# Mirley_USB-UART.net
KiCad netlist of a schematic drawn in EAGLE
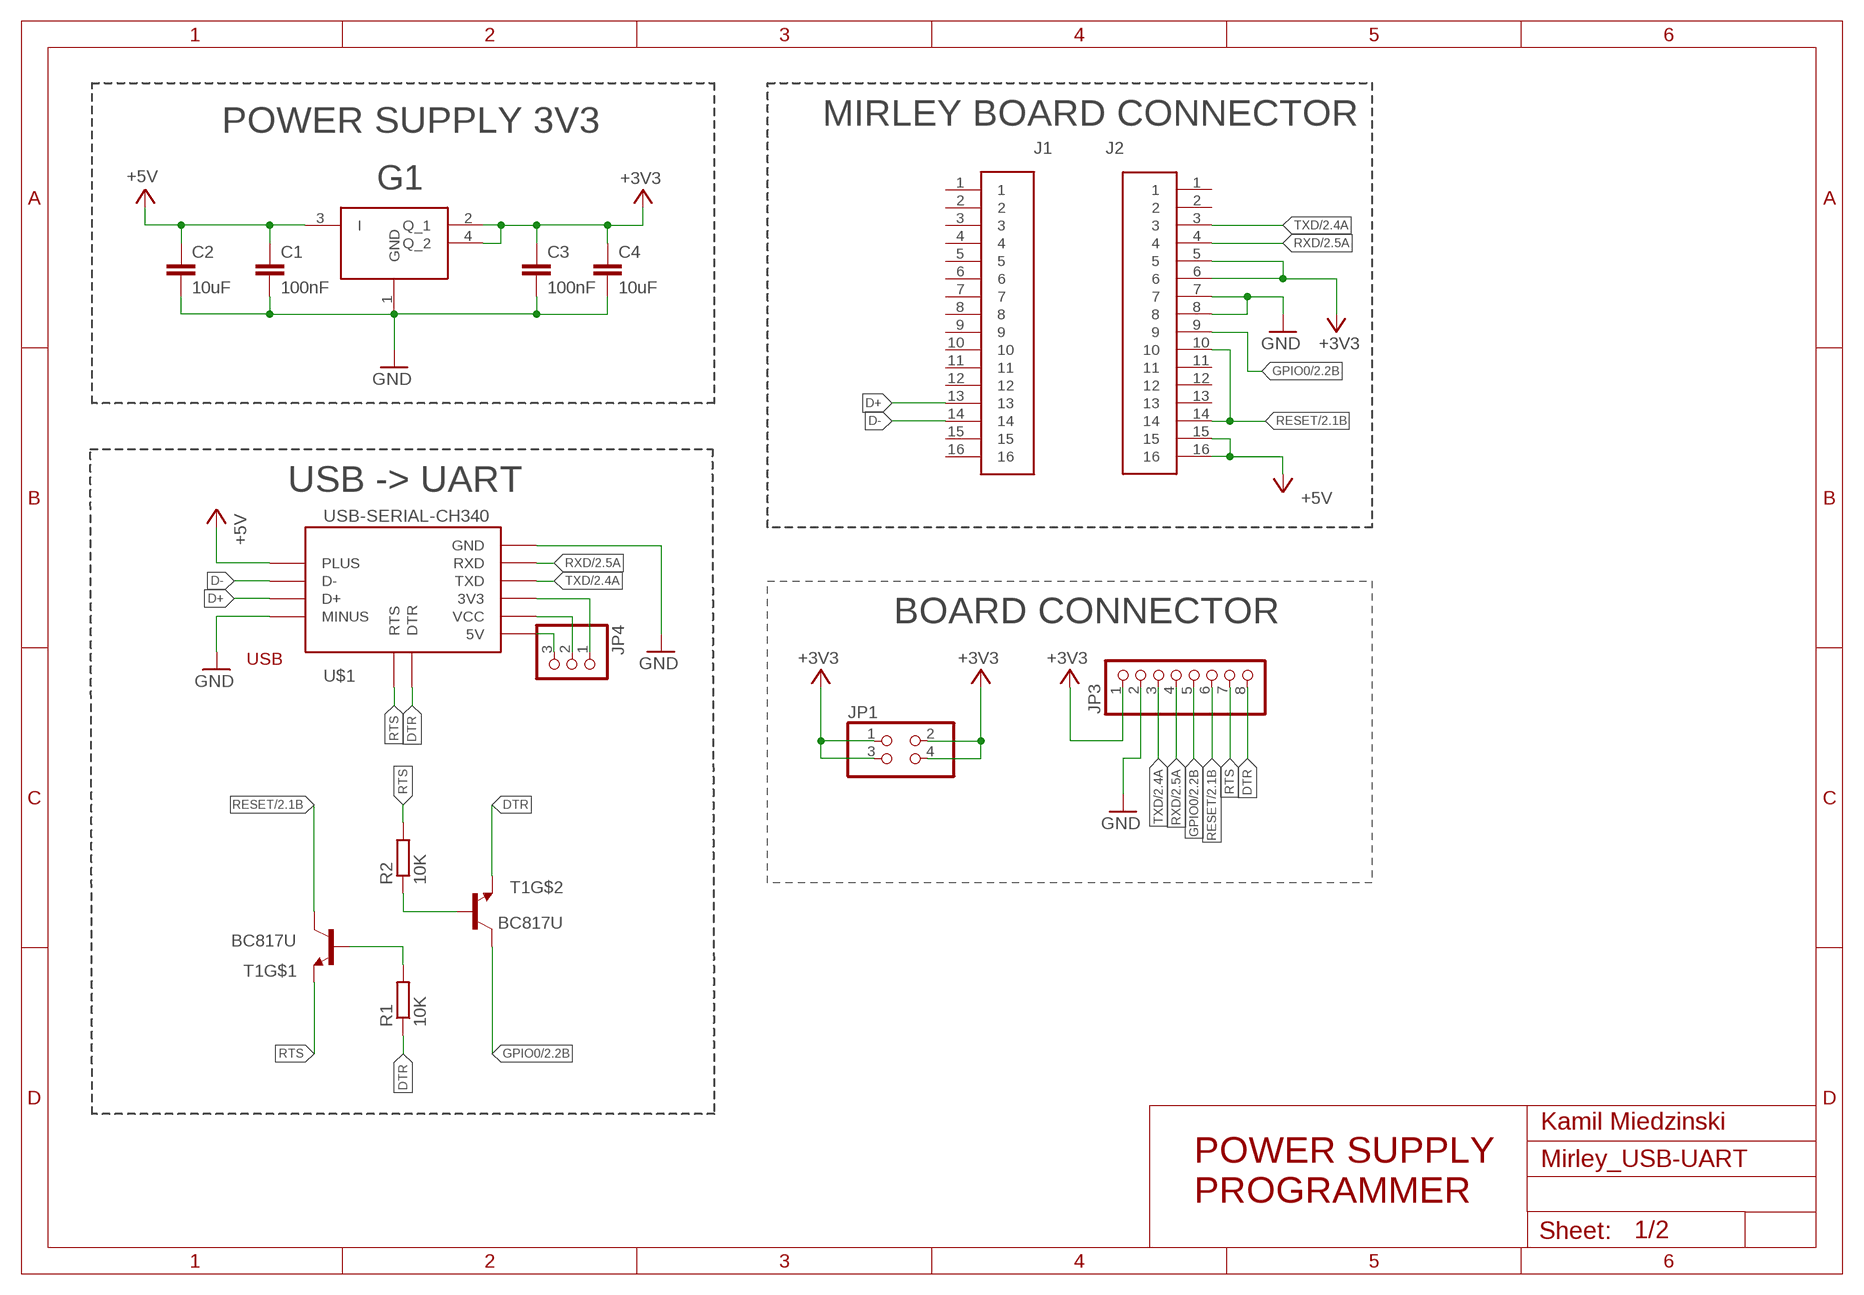
[diagram p0: schematic, sheet 1]
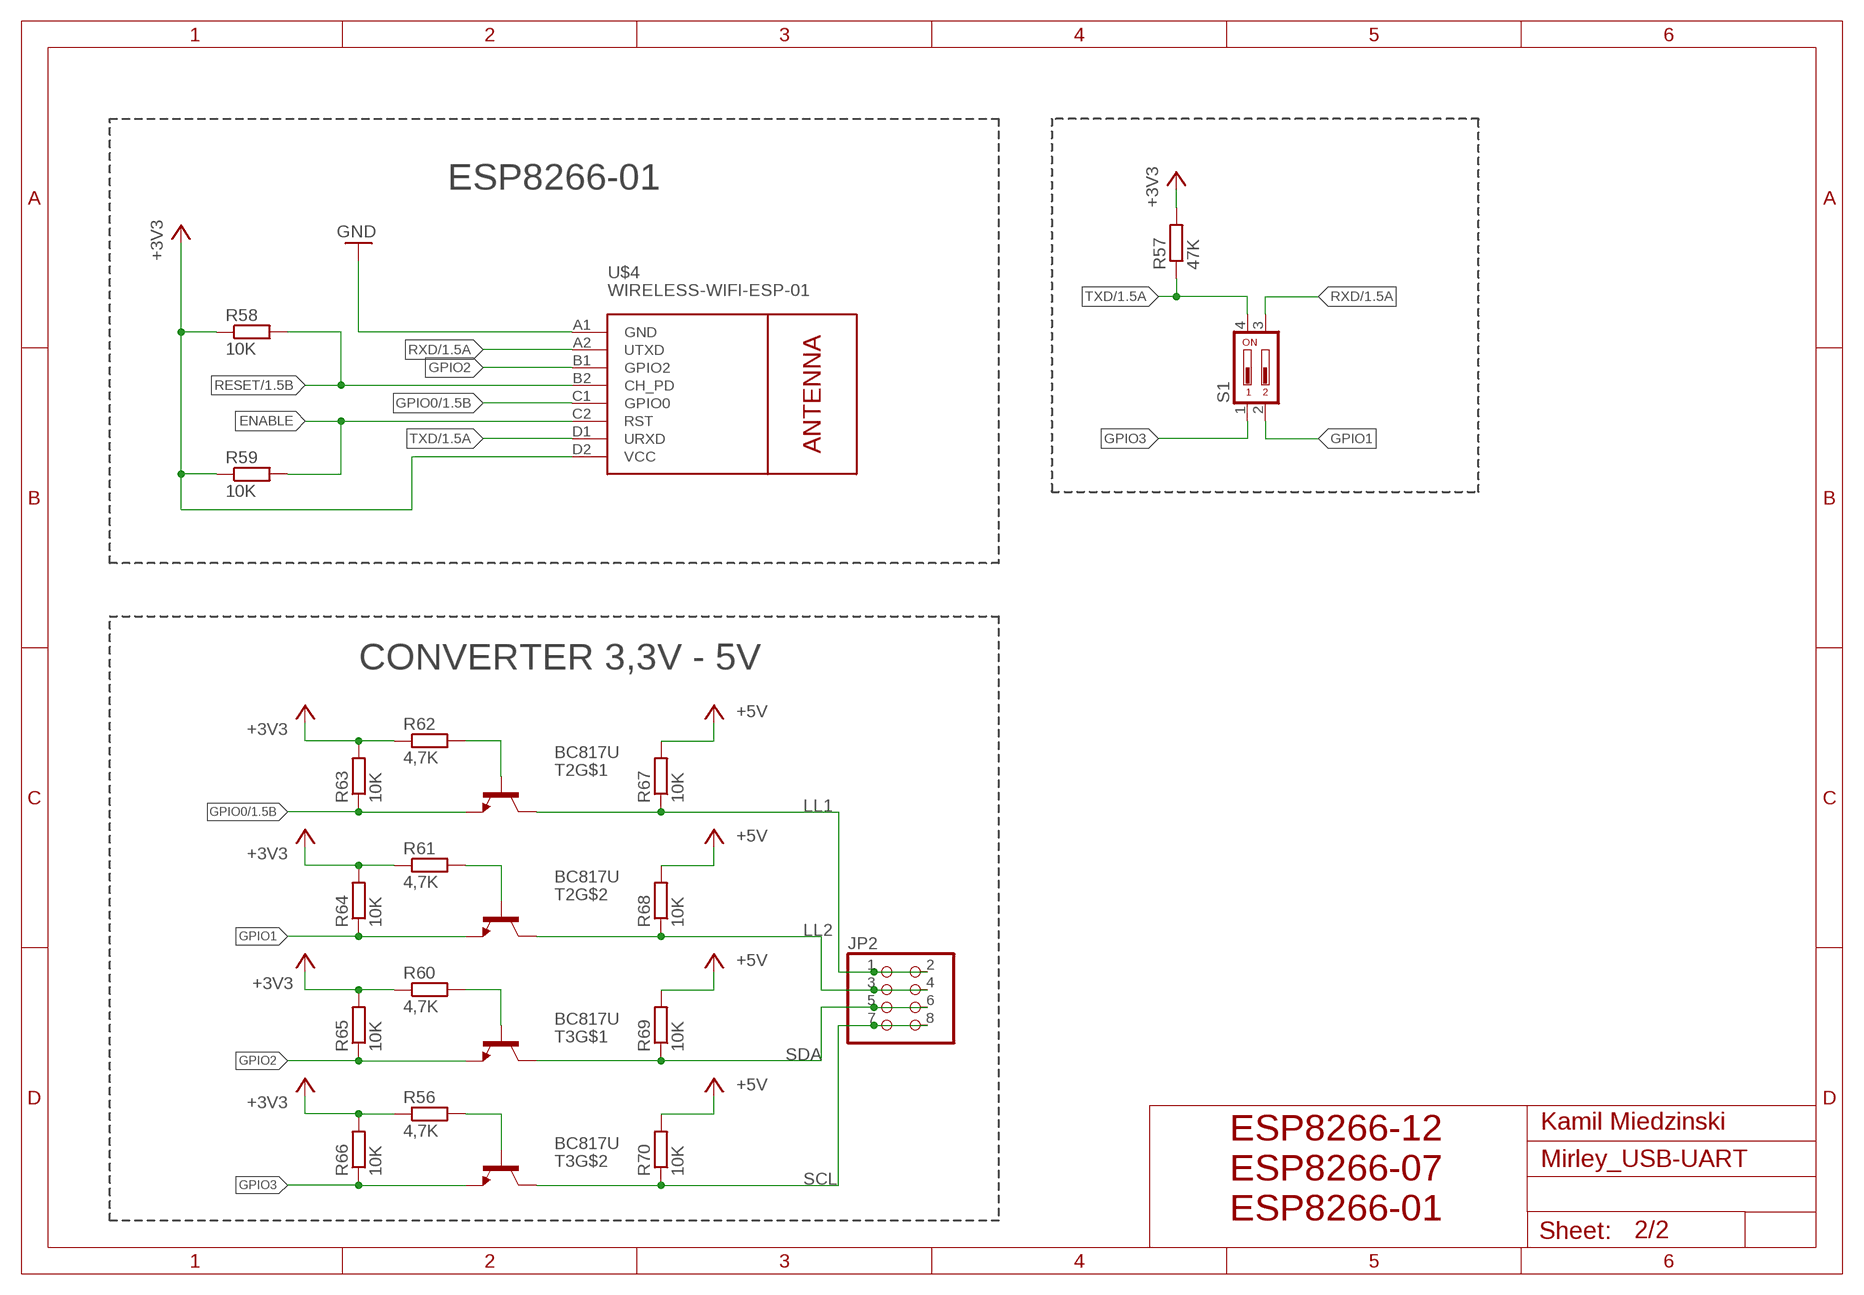
[diagram p1: schematic, sheet 2]

(export (version "E")
  (design (tool "Eeschema 10.0.6"))
  (components
    (comp (ref "JP2")
      (value "PINHD-2X4")
      (footprint "eagle-import:2X04")
      (libsource (lib "eagle-import") (part "PINHD-2X4"))
    )
    (comp (ref "R56")
      (value "4,7K")
      (footprint "eagle-import:R0805")
      (libsource (lib "eagle-import") (part "R-EU_R0805"))
    )
    (comp (ref "R57")
      (value "47K")
      (footprint "eagle-import:R0805")
      (libsource (lib "eagle-import") (part "R-EU_R0805"))
    )
    (comp (ref "R58")
      (value "10K")
      (footprint "eagle-import:R0805")
      (libsource (lib "eagle-import") (part "R-EU_R0805"))
    )
    (comp (ref "R59")
      (value "10K")
      (footprint "eagle-import:R0805")
      (libsource (lib "eagle-import") (part "R-EU_R0805"))
    )
    (comp (ref "R60")
      (value "4,7K")
      (footprint "eagle-import:R0805")
      (libsource (lib "eagle-import") (part "R-EU_R0805"))
    )
    (comp (ref "R61")
      (value "4,7K")
      (footprint "eagle-import:R0805")
      (libsource (lib "eagle-import") (part "R-EU_R0805"))
    )
    (comp (ref "R62")
      (value "4,7K")
      (footprint "eagle-import:R0805")
      (libsource (lib "eagle-import") (part "R-EU_R0805"))
    )
    (comp (ref "R63")
      (value "10K")
      (footprint "eagle-import:R0805")
      (libsource (lib "eagle-import") (part "R-EU_R0805"))
    )
    (comp (ref "R64")
      (value "10K")
      (footprint "eagle-import:R0805")
      (libsource (lib "eagle-import") (part "R-EU_R0805"))
    )
    (comp (ref "R65")
      (value "10K")
      (footprint "eagle-import:R0805")
      (libsource (lib "eagle-import") (part "R-EU_R0805"))
    )
    (comp (ref "R66")
      (value "10K")
      (footprint "eagle-import:R0805")
      (libsource (lib "eagle-import") (part "R-EU_R0805"))
    )
    (comp (ref "R67")
      (value "10K")
      (footprint "eagle-import:R0805")
      (libsource (lib "eagle-import") (part "R-EU_R0805"))
    )
    (comp (ref "R68")
      (value "10K")
      (footprint "eagle-import:R0805")
      (libsource (lib "eagle-import") (part "R-EU_R0805"))
    )
    (comp (ref "R69")
      (value "10K")
      (footprint "eagle-import:R0805")
      (libsource (lib "eagle-import") (part "R-EU_R0805"))
    )
    (comp (ref "R70")
      (value "10K")
      (footprint "eagle-import:R0805")
      (libsource (lib "eagle-import") (part "R-EU_R0805"))
    )
    (comp (ref "S1")
      (value "DIP02YL")
      (footprint "eagle-import:DIP02YL")
      (libsource (lib "eagle-import") (part "DIP02YL"))
    )
    (comp (ref "T2")
      (value "BC817U")
      (footprint "eagle-import:INF-SC74")
      (libsource (lib "eagle-import") (part "BC817U"))
    )
    (comp (ref "T3")
      (value "BC817U")
      (footprint "eagle-import:INF-SC74")
      (libsource (lib "eagle-import") (part "BC817U"))
    )
    (comp (ref "U$4")
      (value "WIRELESS-WIFI-ESP-01")
      (footprint "eagle-import:WIRELESS-WIFI-ESP-01")
      (libsource (lib "eagle-import") (part "WIRELESS-WIFI-ESP-01"))
    )
    (comp (ref "C1")
      (value "100nF")
      (footprint "eagle-import:C0805K")
      (libsource (lib "eagle-import") (part "C-EUC0805K"))
    )
    (comp (ref "C2")
      (value "10uF")
      (footprint "eagle-import:C0805K")
      (libsource (lib "eagle-import") (part "C-EUC0805K"))
    )
    (comp (ref "C3")
      (value "100nF")
      (footprint "eagle-import:C0805K")
      (libsource (lib "eagle-import") (part "C-EUC0805K"))
    )
    (comp (ref "C4")
      (value "10uF")
      (footprint "eagle-import:C0805K")
      (libsource (lib "eagle-import") (part "C-EUC0805K"))
    )
    (comp (ref "G1")
      (value "IFX1117ME_V33")
      (footprint "eagle-import:SOT230P700X170-4N-1")
      (libsource (lib "eagle-import") (part "IFX1117ME_V33"))
    )
    (comp (ref "J1")
      (value "61301611121")
      (footprint "eagle-import:61301611121")
      (fields
        (field (name "DIGIKEY_PART_NUMBER") "732-5327-ND")
        (field (name "MANUFACTURER") "Wurth Electronics Inc.")
        (field (name "CREATED_BY") "PCBLayout.com")
      )
      (libsource (lib "eagle-import") (part "61301611121"))
    )
    (comp (ref "J2")
      (value "61301611121")
      (footprint "eagle-import:61301611121")
      (fields
        (field (name "DIGIKEY_PART_NUMBER") "732-5327-ND")
        (field (name "MANUFACTURER") "Wurth Electronics Inc.")
        (field (name "CREATED_BY") "PCBLayout.com")
      )
      (libsource (lib "eagle-import") (part "61301611121"))
    )
    (comp (ref "JP1")
      (value "PINHD-2X2")
      (footprint "eagle-import:2X02")
      (fields (field (name "SPICEPREFIX") "E"))
      (libsource (lib "eagle-import") (part "PINHD-2X2"))
    )
    (comp (ref "JP3")
      (value "PINHD-1X8")
      (footprint "eagle-import:1X08")
      (libsource (lib "eagle-import") (part "PINHD-1X8"))
    )
    (comp (ref "JP4")
      (value "PINHD-1X3")
      (footprint "eagle-import:1X03")
      (libsource (lib "eagle-import") (part "PINHD-1X3"))
    )
    (comp (ref "R1")
      (value "10K")
      (footprint "eagle-import:R0805")
      (libsource (lib "eagle-import") (part "R-EU_R0805"))
    )
    (comp (ref "R2")
      (value "10K")
      (footprint "eagle-import:R0805")
      (libsource (lib "eagle-import") (part "R-EU_R0805"))
    )
    (comp (ref "T1")
      (value "BC817U")
      (footprint "eagle-import:INF-SC74")
      (libsource (lib "eagle-import") (part "BC817U"))
    )
    (comp (ref "U$1")
      (value "USB-SERIAL-CH340")
      (footprint "eagle-import:USB-SERIAL-CH340")
      (libsource (lib "eagle-import") (part "USB-SERIAL-CH340"))
    )
  )
  (nets
    (net (code "1") (name "+3V3") (class "Default")
      (node (ref "C3") (pin "1") (pinfunction "1_1") (pintype "passive"))
      (node (ref "C4") (pin "1") (pinfunction "1_1") (pintype "passive"))
      (node (ref "G1") (pin "2") (pinfunction "Q_1_2") (pintype "power_in"))
      (node (ref "G1") (pin "4") (pinfunction "Q_2_4") (pintype "power_in"))
      (node (ref "J2") (pin "5") (pinfunction "5_5") (pintype "passive"))
      (node (ref "J2") (pin "6") (pinfunction "6_6") (pintype "passive"))
      (node (ref "JP1") (pin "1") (pinfunction "1_1") (pintype "passive"))
      (node (ref "JP1") (pin "2") (pinfunction "2_2") (pintype "passive"))
      (node (ref "JP1") (pin "3") (pinfunction "3_3") (pintype "passive"))
      (node (ref "JP1") (pin "4") (pinfunction "4_4") (pintype "passive"))
      (node (ref "JP3") (pin "1") (pinfunction "1_1") (pintype "passive"))
      (node (ref "R56") (pin "1") (pinfunction "1_1") (pintype "passive"))
      (node (ref "R57") (pin "2") (pinfunction "2_2") (pintype "passive"))
      (node (ref "R58") (pin "1") (pinfunction "1_1") (pintype "passive"))
      (node (ref "R59") (pin "1") (pinfunction "1_1") (pintype "passive"))
      (node (ref "R60") (pin "1") (pinfunction "1_1") (pintype "passive"))
      (node (ref "R61") (pin "1") (pinfunction "1_1") (pintype "passive"))
      (node (ref "R62") (pin "1") (pinfunction "1_1") (pintype "passive"))
      (node (ref "R63") (pin "2") (pinfunction "2_2") (pintype "passive"))
      (node (ref "R64") (pin "2") (pinfunction "2_2") (pintype "passive"))
      (node (ref "R65") (pin "2") (pinfunction "2_2") (pintype "passive"))
      (node (ref "R66") (pin "2") (pinfunction "2_2") (pintype "passive"))
      (node (ref "U$4") (pin "D2") (pinfunction "VCC_D2") (pintype "power_in"))
    )
    (net (code "2") (name "+5V") (class "Default")
      (node (ref "C1") (pin "1") (pinfunction "1_1") (pintype "passive"))
      (node (ref "C2") (pin "1") (pinfunction "1_1") (pintype "passive"))
      (node (ref "G1") (pin "3") (pinfunction "I_3") (pintype "power_in"))
      (node (ref "J2") (pin "15") (pinfunction "15_15") (pintype "passive"))
      (node (ref "J2") (pin "16") (pinfunction "16_16") (pintype "passive"))
      (node (ref "R67") (pin "2") (pinfunction "2_2") (pintype "passive"))
      (node (ref "R68") (pin "2") (pinfunction "2_2") (pintype "passive"))
      (node (ref "R69") (pin "2") (pinfunction "2_2") (pintype "passive"))
      (node (ref "R70") (pin "2") (pinfunction "2_2") (pintype "passive"))
      (node (ref "U$1") (pin "PLUS") (pinfunction "PLUS_PLUS") (pintype "bidirectional"))
    )
    (net (code "3") (name "D+") (class "Default")
      (node (ref "J1") (pin "13") (pinfunction "13_13") (pintype "passive"))
      (node (ref "U$1") (pin "D+") (pinfunction "D+_D+") (pintype "bidirectional"))
    )
    (net (code "4") (name "D-") (class "Default")
      (node (ref "J1") (pin "14") (pinfunction "14_14") (pintype "passive"))
      (node (ref "U$1") (pin "D-") (pinfunction "D-_D-") (pintype "bidirectional"))
    )
    (net (code "5") (name "DTR") (class "Default")
      (node (ref "JP3") (pin "8") (pinfunction "8_8") (pintype "passive"))
      (node (ref "R1") (pin "1") (pinfunction "1_1") (pintype "passive"))
      (node (ref "T1") (pin "4") (pinfunction "E_4") (pintype "passive"))
      (node (ref "U$1") (pin "DTR") (pinfunction "DTR_DTR") (pintype "bidirectional"))
    )
    (net (code "6") (name "ENABLE") (class "Default")
      (node (ref "R59") (pin "2") (pinfunction "2_2") (pintype "passive"))
      (node (ref "U$4") (pin "C2") (pinfunction "RST_C2") (pintype "bidirectional"))
    )
    (net (code "7") (name "GND") (class "Default")
      (node (ref "C1") (pin "2") (pinfunction "2_2") (pintype "passive"))
      (node (ref "C2") (pin "2") (pinfunction "2_2") (pintype "passive"))
      (node (ref "C3") (pin "2") (pinfunction "2_2") (pintype "passive"))
      (node (ref "C4") (pin "2") (pinfunction "2_2") (pintype "passive"))
      (node (ref "G1") (pin "1") (pinfunction "GND_1") (pintype "power_in"))
      (node (ref "J2") (pin "7") (pinfunction "7_7") (pintype "passive"))
      (node (ref "J2") (pin "8") (pinfunction "8_8") (pintype "passive"))
      (node (ref "JP3") (pin "2") (pinfunction "2_2") (pintype "passive"))
      (node (ref "U$1") (pin "GND") (pinfunction "GND_GND") (pintype "power_in"))
      (node (ref "U$1") (pin "MINUS") (pinfunction "MINUS_MINUS") (pintype "bidirectional"))
      (node (ref "U$4") (pin "A1") (pinfunction "GND_A1") (pintype "power_in"))
    )
    (net (code "8") (name "GPIO0") (class "Default")
      (node (ref "J2") (pin "9") (pinfunction "9_9") (pintype "passive"))
      (node (ref "JP3") (pin "5") (pinfunction "5_5") (pintype "passive"))
      (node (ref "R63") (pin "1") (pinfunction "1_1") (pintype "passive"))
      (node (ref "T1") (pin "3") (pinfunction "C_3") (pintype "passive"))
      (node (ref "T2") (pin "1") (pinfunction "E_1") (pintype "passive"))
      (node (ref "U$4") (pin "C1") (pinfunction "GPIO0_C1") (pintype "bidirectional"))
    )
    (net (code "9") (name "GPIO1") (class "Default")
      (node (ref "R64") (pin "1") (pinfunction "1_1") (pintype "passive"))
      (node (ref "S1") (pin "2") (pinfunction "2_2") (pintype "passive"))
      (node (ref "T2") (pin "4") (pinfunction "E_4") (pintype "passive"))
    )
    (net (code "10") (name "GPIO2") (class "Default")
      (node (ref "R65") (pin "1") (pinfunction "1_1") (pintype "passive"))
      (node (ref "T3") (pin "1") (pinfunction "E_1") (pintype "passive"))
      (node (ref "U$4") (pin "B1") (pinfunction "GPIO2_B1") (pintype "bidirectional"))
    )
    (net (code "11") (name "GPIO3") (class "Default")
      (node (ref "R66") (pin "1") (pinfunction "1_1") (pintype "passive"))
      (node (ref "S1") (pin "1") (pinfunction "1_1") (pintype "passive"))
      (node (ref "T3") (pin "4") (pinfunction "E_4") (pintype "passive"))
    )
    (net (code "12") (name "LL1") (class "Default")
      (node (ref "JP2") (pin "1") (pinfunction "1_1") (pintype "passive"))
      (node (ref "JP2") (pin "2") (pinfunction "2_2") (pintype "passive"))
      (node (ref "R67") (pin "1") (pinfunction "1_1") (pintype "passive"))
      (node (ref "T2") (pin "6") (pinfunction "C_6") (pintype "passive"))
    )
    (net (code "13") (name "LL2") (class "Default")
      (node (ref "JP2") (pin "3") (pinfunction "3_3") (pintype "passive"))
      (node (ref "JP2") (pin "4") (pinfunction "4_4") (pintype "passive"))
      (node (ref "R68") (pin "1") (pinfunction "1_1") (pintype "passive"))
      (node (ref "T2") (pin "3") (pinfunction "C_3") (pintype "passive"))
    )
    (net (code "14") (name "Net-(JP4-Pad1)") (class "Default")
      (node (ref "JP4") (pin "1") (pinfunction "1_1") (pintype "passive"))
      (node (ref "U$1") (pin "3V3") (pinfunction "3V3_3V3") (pintype "bidirectional"))
    )
    (net (code "15") (name "Net-(JP4-Pad2)") (class "Default")
      (node (ref "JP4") (pin "2") (pinfunction "2_2") (pintype "passive"))
      (node (ref "U$1") (pin "VCC") (pinfunction "VCC_VCC") (pintype "bidirectional"))
    )
    (net (code "16") (name "Net-(JP4-Pad3)") (class "Default")
      (node (ref "JP4") (pin "3") (pinfunction "3_3") (pintype "passive"))
      (node (ref "U$1") (pin "5V") (pinfunction "5V_5V") (pintype "power_in"))
    )
    (net (code "17") (name "Net-(T1A-B)") (class "Default")
      (node (ref "R1") (pin "2") (pinfunction "2_2") (pintype "passive"))
      (node (ref "T1") (pin "2") (pinfunction "B_2") (pintype "passive"))
    )
    (net (code "18") (name "Net-(T1B-B)") (class "Default")
      (node (ref "R2") (pin "1") (pinfunction "1_1") (pintype "passive"))
      (node (ref "T1") (pin "5") (pinfunction "B_5") (pintype "passive"))
    )
    (net (code "19") (name "Net-(T2A-B)") (class "Default")
      (node (ref "R62") (pin "2") (pinfunction "2_2") (pintype "passive"))
      (node (ref "T2") (pin "2") (pinfunction "B_2") (pintype "passive"))
    )
    (net (code "20") (name "Net-(T2B-B)") (class "Default")
      (node (ref "R61") (pin "2") (pinfunction "2_2") (pintype "passive"))
      (node (ref "T2") (pin "5") (pinfunction "B_5") (pintype "passive"))
    )
    (net (code "21") (name "Net-(T3A-B)") (class "Default")
      (node (ref "R60") (pin "2") (pinfunction "2_2") (pintype "passive"))
      (node (ref "T3") (pin "2") (pinfunction "B_2") (pintype "passive"))
    )
    (net (code "22") (name "Net-(T3B-B)") (class "Default")
      (node (ref "R56") (pin "2") (pinfunction "2_2") (pintype "passive"))
      (node (ref "T3") (pin "5") (pinfunction "B_5") (pintype "passive"))
    )
    (net (code "23") (name "RESET") (class "Default")
      (node (ref "J2") (pin "10") (pinfunction "10_10") (pintype "passive"))
      (node (ref "J2") (pin "14") (pinfunction "14_14") (pintype "passive"))
      (node (ref "JP3") (pin "6") (pinfunction "6_6") (pintype "passive"))
      (node (ref "R58") (pin "2") (pinfunction "2_2") (pintype "passive"))
      (node (ref "T1") (pin "6") (pinfunction "C_6") (pintype "passive"))
      (node (ref "U$4") (pin "B2") (pinfunction "CH_PD_B2") (pintype "bidirectional"))
    )
    (net (code "24") (name "RTS") (class "Default")
      (node (ref "JP3") (pin "7") (pinfunction "7_7") (pintype "passive"))
      (node (ref "R2") (pin "2") (pinfunction "2_2") (pintype "passive"))
      (node (ref "T1") (pin "1") (pinfunction "E_1") (pintype "passive"))
      (node (ref "U$1") (pin "RTS") (pinfunction "RTS_RTS") (pintype "bidirectional"))
    )
    (net (code "25") (name "RXD") (class "Default")
      (node (ref "J2") (pin "4") (pinfunction "4_4") (pintype "passive"))
      (node (ref "JP3") (pin "4") (pinfunction "4_4") (pintype "passive"))
      (node (ref "S1") (pin "3") (pinfunction "3_3") (pintype "passive"))
      (node (ref "U$1") (pin "RXD") (pinfunction "RXD_RXD") (pintype "power_in"))
      (node (ref "U$4") (pin "A2") (pinfunction "UTXD_A2") (pintype "bidirectional"))
    )
    (net (code "26") (name "SCL") (class "Default")
      (node (ref "JP2") (pin "7") (pinfunction "7_7") (pintype "passive"))
      (node (ref "JP2") (pin "8") (pinfunction "8_8") (pintype "passive"))
      (node (ref "R70") (pin "1") (pinfunction "1_1") (pintype "passive"))
      (node (ref "T3") (pin "3") (pinfunction "C_3") (pintype "passive"))
    )
    (net (code "27") (name "SDA") (class "Default")
      (node (ref "JP2") (pin "5") (pinfunction "5_5") (pintype "passive"))
      (node (ref "JP2") (pin "6") (pinfunction "6_6") (pintype "passive"))
      (node (ref "R69") (pin "1") (pinfunction "1_1") (pintype "passive"))
      (node (ref "T3") (pin "6") (pinfunction "C_6") (pintype "passive"))
    )
    (net (code "28") (name "TXD") (class "Default")
      (node (ref "J2") (pin "3") (pinfunction "3_3") (pintype "passive"))
      (node (ref "JP3") (pin "3") (pinfunction "3_3") (pintype "passive"))
      (node (ref "R57") (pin "1") (pinfunction "1_1") (pintype "passive"))
      (node (ref "S1") (pin "4") (pinfunction "4_4") (pintype "passive"))
      (node (ref "U$1") (pin "TXD") (pinfunction "TXD_TXD") (pintype "bidirectional"))
      (node (ref "U$4") (pin "D1") (pinfunction "URXD_D1") (pintype "bidirectional"))
    )
    (net (code "29") (name "unconnected-(J1-Pad1)") (class "Default")
      (node (ref "J1") (pin "1") (pinfunction "1_1") (pintype "passive"))
    )
    (net (code "30") (name "unconnected-(J1-Pad2)") (class "Default")
      (node (ref "J1") (pin "2") (pinfunction "2_2") (pintype "passive"))
    )
    (net (code "31") (name "unconnected-(J1-Pad3)") (class "Default")
      (node (ref "J1") (pin "3") (pinfunction "3_3") (pintype "passive"))
    )
    (net (code "32") (name "unconnected-(J1-Pad4)") (class "Default")
      (node (ref "J1") (pin "4") (pinfunction "4_4") (pintype "passive"))
    )
    (net (code "33") (name "unconnected-(J1-Pad5)") (class "Default")
      (node (ref "J1") (pin "5") (pinfunction "5_5") (pintype "passive"))
    )
    (net (code "34") (name "unconnected-(J1-Pad6)") (class "Default")
      (node (ref "J1") (pin "6") (pinfunction "6_6") (pintype "passive"))
    )
    (net (code "35") (name "unconnected-(J1-Pad7)") (class "Default")
      (node (ref "J1") (pin "7") (pinfunction "7_7") (pintype "passive"))
    )
    (net (code "36") (name "unconnected-(J1-Pad8)") (class "Default")
      (node (ref "J1") (pin "8") (pinfunction "8_8") (pintype "passive"))
    )
    (net (code "37") (name "unconnected-(J1-Pad9)") (class "Default")
      (node (ref "J1") (pin "9") (pinfunction "9_9") (pintype "passive"))
    )
    (net (code "38") (name "unconnected-(J1-Pad10)") (class "Default")
      (node (ref "J1") (pin "10") (pinfunction "10_10") (pintype "passive"))
    )
    (net (code "39") (name "unconnected-(J1-Pad11)") (class "Default")
      (node (ref "J1") (pin "11") (pinfunction "11_11") (pintype "passive"))
    )
    (net (code "40") (name "unconnected-(J1-Pad12)") (class "Default")
      (node (ref "J1") (pin "12") (pinfunction "12_12") (pintype "passive"))
    )
    (net (code "41") (name "unconnected-(J1-Pad15)") (class "Default")
      (node (ref "J1") (pin "15") (pinfunction "15_15") (pintype "passive"))
    )
    (net (code "42") (name "unconnected-(J1-Pad16)") (class "Default")
      (node (ref "J1") (pin "16") (pinfunction "16_16") (pintype "passive"))
    )
    (net (code "43") (name "unconnected-(J2-Pad1)") (class "Default")
      (node (ref "J2") (pin "1") (pinfunction "1_1") (pintype "passive"))
    )
    (net (code "44") (name "unconnected-(J2-Pad2)") (class "Default")
      (node (ref "J2") (pin "2") (pinfunction "2_2") (pintype "passive"))
    )
    (net (code "45") (name "unconnected-(J2-Pad11)") (class "Default")
      (node (ref "J2") (pin "11") (pinfunction "11_11") (pintype "passive"))
    )
    (net (code "46") (name "unconnected-(J2-Pad12)") (class "Default")
      (node (ref "J2") (pin "12") (pinfunction "12_12") (pintype "passive"))
    )
    (net (code "47") (name "unconnected-(J2-Pad13)") (class "Default")
      (node (ref "J2") (pin "13") (pinfunction "13_13") (pintype "passive"))
    )
  )
)
